# firefly-ice-blue-fixture.net
KiCad netlist of a schematic drawn in EAGLE
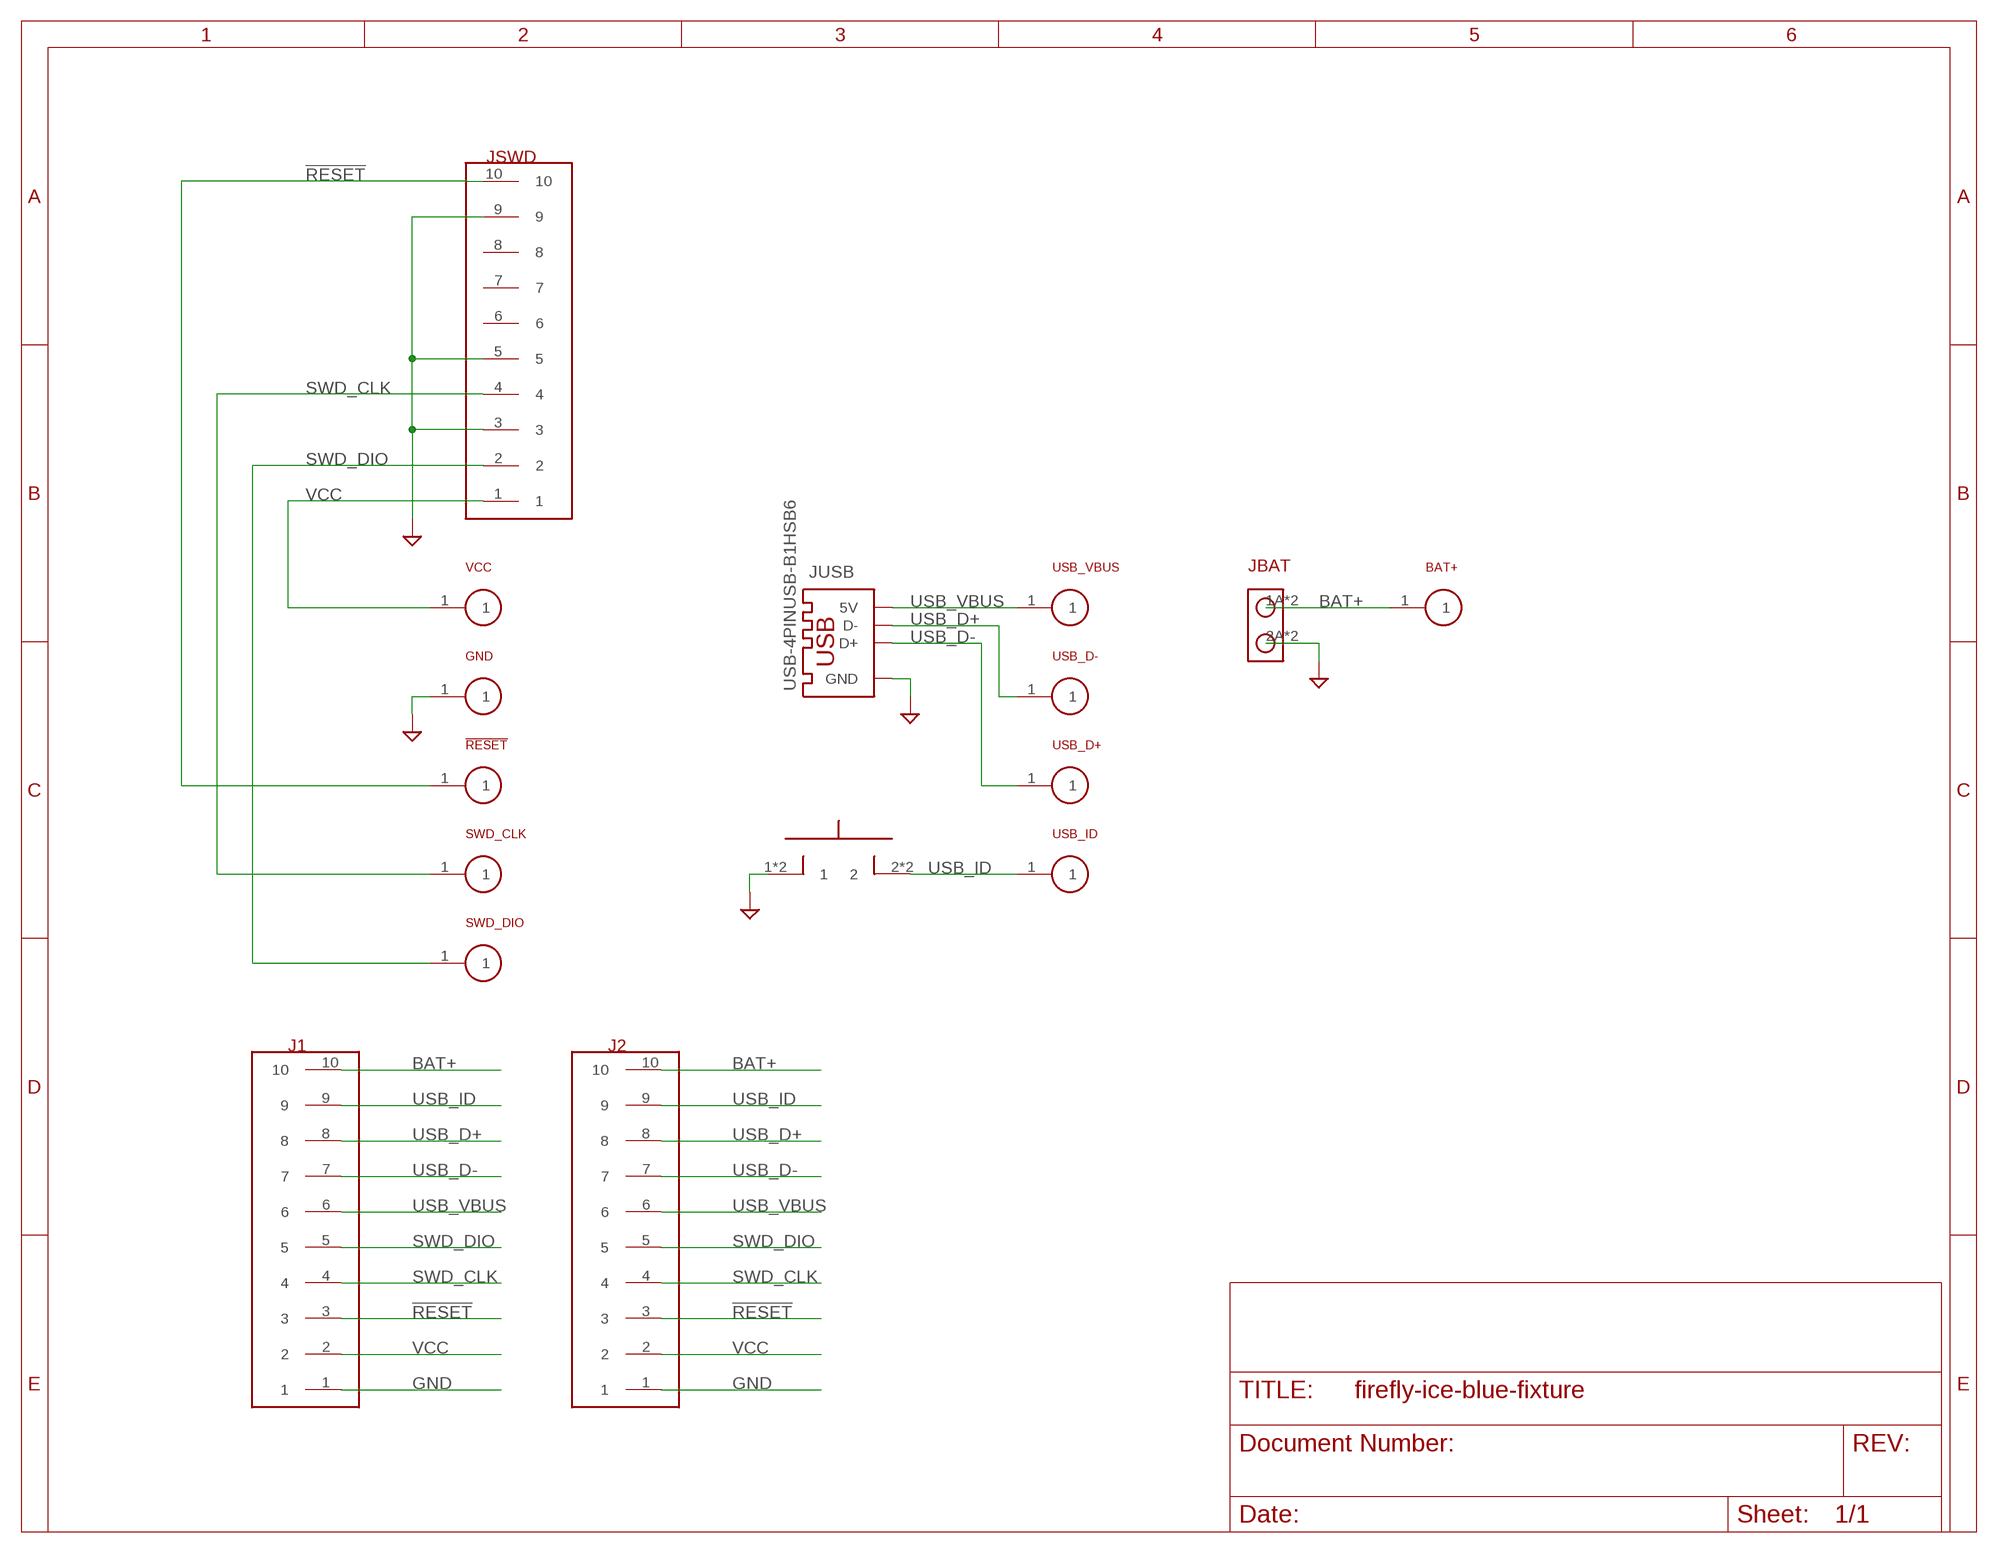
[diagram p0: schematic, sheet 1]

(export (version "E")
  (design (tool "Eeschema 10.0.6"))
  (components
    (comp (ref "!RESET")
      (value "TARGET-PINPROBE-0985")
      (footprint "eagle-import:PROBE-0985")
      (libsource (lib "eagle-import") (part "TARGET-PINPROBE-0985"))
    )
    (comp (ref "BAT+")
      (value "TARGET-PINPROBE-0985")
      (footprint "eagle-import:PROBE-0985")
      (libsource (lib "eagle-import") (part "TARGET-PINPROBE-0985"))
    )
    (comp (ref "GND")
      (value "TARGET-PINPROBE-0985")
      (footprint "eagle-import:PROBE-0985")
      (libsource (lib "eagle-import") (part "TARGET-PINPROBE-0985"))
    )
    (comp (ref "J1")
      (value "CON-10")
      (footprint "eagle-import:CON-HEADER-10")
      (libsource (lib "eagle-import") (part "CON-10"))
    )
    (comp (ref "J2")
      (value "CON-10")
      (footprint "eagle-import:CON-HEADER-10")
      (libsource (lib "eagle-import") (part "CON-10"))
    )
    (comp (ref "JBAT")
      (value "CON-220020303-D021B01LF")
      (footprint "eagle-import:20020303-D021B01LF")
      (fields (field (name "MANUFACTURER") "FCI"))
      (libsource (lib "eagle-import") (part "CON-220020303-D021B01LF"))
    )
    (comp (ref "JSWD")
      (value "CON-10SWD")
      (footprint "eagle-import:SWD-10")
      (libsource (lib "eagle-import") (part "CON-10SWD"))
    )
    (comp (ref "JUSB")
      (value "USB-4PINUSB-B1HSB6")
      (footprint "eagle-import:USB-B1HSB6")
      (fields (field (name "MANUFACTURER") "On Shore Technology Inc"))
      (libsource (lib "eagle-import") (part "USB-4PINUSB-B1HSB6"))
    )
    (comp (ref "SRES")
      (value "SPST-NOKS-01Q-01")
      (footprint "eagle-import:KS-01Q-01")
      (fields (field (name "MANUFACTURER") "E-Switch"))
      (libsource (lib "eagle-import") (part "SPST-NOKS-01Q-01"))
    )
    (comp (ref "SWD_CLK")
      (value "TARGET-PINPROBE-0985")
      (footprint "eagle-import:PROBE-0985")
      (libsource (lib "eagle-import") (part "TARGET-PINPROBE-0985"))
    )
    (comp (ref "SWD_DIO")
      (value "TARGET-PINPROBE-0985")
      (footprint "eagle-import:PROBE-0985")
      (libsource (lib "eagle-import") (part "TARGET-PINPROBE-0985"))
    )
    (comp (ref "USB_D+")
      (value "TARGET-PINPROBE-0985")
      (footprint "eagle-import:PROBE-0985")
      (libsource (lib "eagle-import") (part "TARGET-PINPROBE-0985"))
    )
    (comp (ref "USB_D-")
      (value "TARGET-PINPROBE-0985")
      (footprint "eagle-import:PROBE-0985")
      (libsource (lib "eagle-import") (part "TARGET-PINPROBE-0985"))
    )
    (comp (ref "USB_ID")
      (value "TARGET-PINPROBE-0985")
      (footprint "eagle-import:PROBE-0985")
      (libsource (lib "eagle-import") (part "TARGET-PINPROBE-0985"))
    )
    (comp (ref "USB_VBUS")
      (value "TARGET-PINPROBE-0985")
      (footprint "eagle-import:PROBE-0985")
      (libsource (lib "eagle-import") (part "TARGET-PINPROBE-0985"))
    )
    (comp (ref "VCC")
      (value "TARGET-PINPROBE-0985")
      (footprint "eagle-import:PROBE-0985")
      (libsource (lib "eagle-import") (part "TARGET-PINPROBE-0985"))
    )
  )
  (nets
    (net (code "1") (name "/BAT+") (class "Default")
      (node (ref "BAT+") (pin "1") (pinfunction "1_1") (pintype "bidirectional"))
      (node (ref "J1") (pin "10") (pinfunction "10_10") (pintype "bidirectional"))
      (node (ref "J2") (pin "10") (pinfunction "10_10") (pintype "bidirectional"))
      (node (ref "JBAT") (pin "1A") (pinfunction "1_1A") (pintype "bidirectional"))
      (node (ref "JBAT") (pin "1B") (pinfunction "1_1B") (pintype "bidirectional"))
    )
    (net (code "2") (name "/SWD_CLK") (class "Default")
      (node (ref "J1") (pin "4") (pinfunction "4_4") (pintype "bidirectional"))
      (node (ref "J2") (pin "4") (pinfunction "4_4") (pintype "bidirectional"))
      (node (ref "JSWD") (pin "4") (pinfunction "4_4") (pintype "bidirectional"))
      (node (ref "SWD_CLK") (pin "1") (pinfunction "1_1") (pintype "bidirectional"))
    )
    (net (code "3") (name "/SWD_DIO") (class "Default")
      (node (ref "J1") (pin "5") (pinfunction "5_5") (pintype "bidirectional"))
      (node (ref "J2") (pin "5") (pinfunction "5_5") (pintype "bidirectional"))
      (node (ref "JSWD") (pin "2") (pinfunction "2_2") (pintype "bidirectional"))
      (node (ref "SWD_DIO") (pin "1") (pinfunction "1_1") (pintype "bidirectional"))
    )
    (net (code "4") (name "/USB_D+") (class "Default")
      (node (ref "J1") (pin "8") (pinfunction "8_8") (pintype "bidirectional"))
      (node (ref "J2") (pin "8") (pinfunction "8_8") (pintype "bidirectional"))
      (node (ref "JUSB") (pin "2") (pinfunction "D-_2") (pintype "bidirectional"))
      (node (ref "USB_D-") (pin "1") (pinfunction "1_1") (pintype "bidirectional"))
    )
    (net (code "5") (name "/USB_D-") (class "Default")
      (node (ref "J1") (pin "7") (pinfunction "7_7") (pintype "bidirectional"))
      (node (ref "J2") (pin "7") (pinfunction "7_7") (pintype "bidirectional"))
      (node (ref "JUSB") (pin "3") (pinfunction "D+_3") (pintype "bidirectional"))
      (node (ref "USB_D+") (pin "1") (pinfunction "1_1") (pintype "bidirectional"))
    )
    (net (code "6") (name "/USB_ID") (class "Default")
      (node (ref "J1") (pin "9") (pinfunction "9_9") (pintype "bidirectional"))
      (node (ref "J2") (pin "9") (pinfunction "9_9") (pintype "bidirectional"))
      (node (ref "SRES") (pin "2") (pinfunction "2_2") (pintype "bidirectional"))
      (node (ref "SRES") (pin "4") (pinfunction "2_4") (pintype "bidirectional"))
      (node (ref "USB_ID") (pin "1") (pinfunction "1_1") (pintype "bidirectional"))
    )
    (net (code "7") (name "/USB_VBUS") (class "Default")
      (node (ref "J1") (pin "6") (pinfunction "6_6") (pintype "bidirectional"))
      (node (ref "J2") (pin "6") (pinfunction "6_6") (pintype "bidirectional"))
      (node (ref "JUSB") (pin "1") (pinfunction "5V_1") (pintype "bidirectional"))
      (node (ref "USB_VBUS") (pin "1") (pinfunction "1_1") (pintype "bidirectional"))
    )
    (net (code "8") (name "/VCC") (class "Default")
      (node (ref "J1") (pin "2") (pinfunction "2_2") (pintype "bidirectional"))
      (node (ref "J2") (pin "2") (pinfunction "2_2") (pintype "bidirectional"))
      (node (ref "JSWD") (pin "1") (pinfunction "1_1") (pintype "bidirectional"))
      (node (ref "VCC") (pin "1") (pinfunction "1_1") (pintype "bidirectional"))
    )
    (net (code "9") (name "/~{RESET}") (class "Default")
      (node (ref "!RESET") (pin "1") (pinfunction "1_1") (pintype "bidirectional"))
      (node (ref "J1") (pin "3") (pinfunction "3_3") (pintype "bidirectional"))
      (node (ref "J2") (pin "3") (pinfunction "3_3") (pintype "bidirectional"))
      (node (ref "JSWD") (pin "10") (pinfunction "10_10") (pintype "bidirectional"))
    )
    (net (code "10") (name "GND") (class "Default")
      (node (ref "GND") (pin "1") (pinfunction "1_1") (pintype "bidirectional"))
      (node (ref "J1") (pin "1") (pinfunction "1_1") (pintype "bidirectional"))
      (node (ref "J2") (pin "1") (pinfunction "1_1") (pintype "bidirectional"))
      (node (ref "JBAT") (pin "2A") (pinfunction "2_2A") (pintype "bidirectional"))
      (node (ref "JBAT") (pin "2B") (pinfunction "2_2B") (pintype "bidirectional"))
      (node (ref "JSWD") (pin "3") (pinfunction "3_3") (pintype "bidirectional"))
      (node (ref "JSWD") (pin "5") (pinfunction "5_5") (pintype "bidirectional"))
      (node (ref "JSWD") (pin "9") (pinfunction "9_9") (pintype "bidirectional"))
      (node (ref "JUSB") (pin "4") (pinfunction "GND_4") (pintype "bidirectional"))
      (node (ref "SRES") (pin "1") (pinfunction "1_1") (pintype "bidirectional"))
      (node (ref "SRES") (pin "3") (pinfunction "1_3") (pintype "bidirectional"))
    )
    (net (code "11") (name "unconnected-(JSWD-Pad6)") (class "Default")
      (node (ref "JSWD") (pin "6") (pinfunction "6_6") (pintype "bidirectional"))
    )
    (net (code "12") (name "unconnected-(JSWD-Pad7)") (class "Default")
      (node (ref "JSWD") (pin "7") (pinfunction "7_7") (pintype "bidirectional"))
    )
    (net (code "13") (name "unconnected-(JSWD-Pad8)") (class "Default")
      (node (ref "JSWD") (pin "8") (pinfunction "8_8") (pintype "bidirectional"))
    )
  )
)
